# uStatusBoard.net
KiCad netlist of a schematic drawn in EAGLE
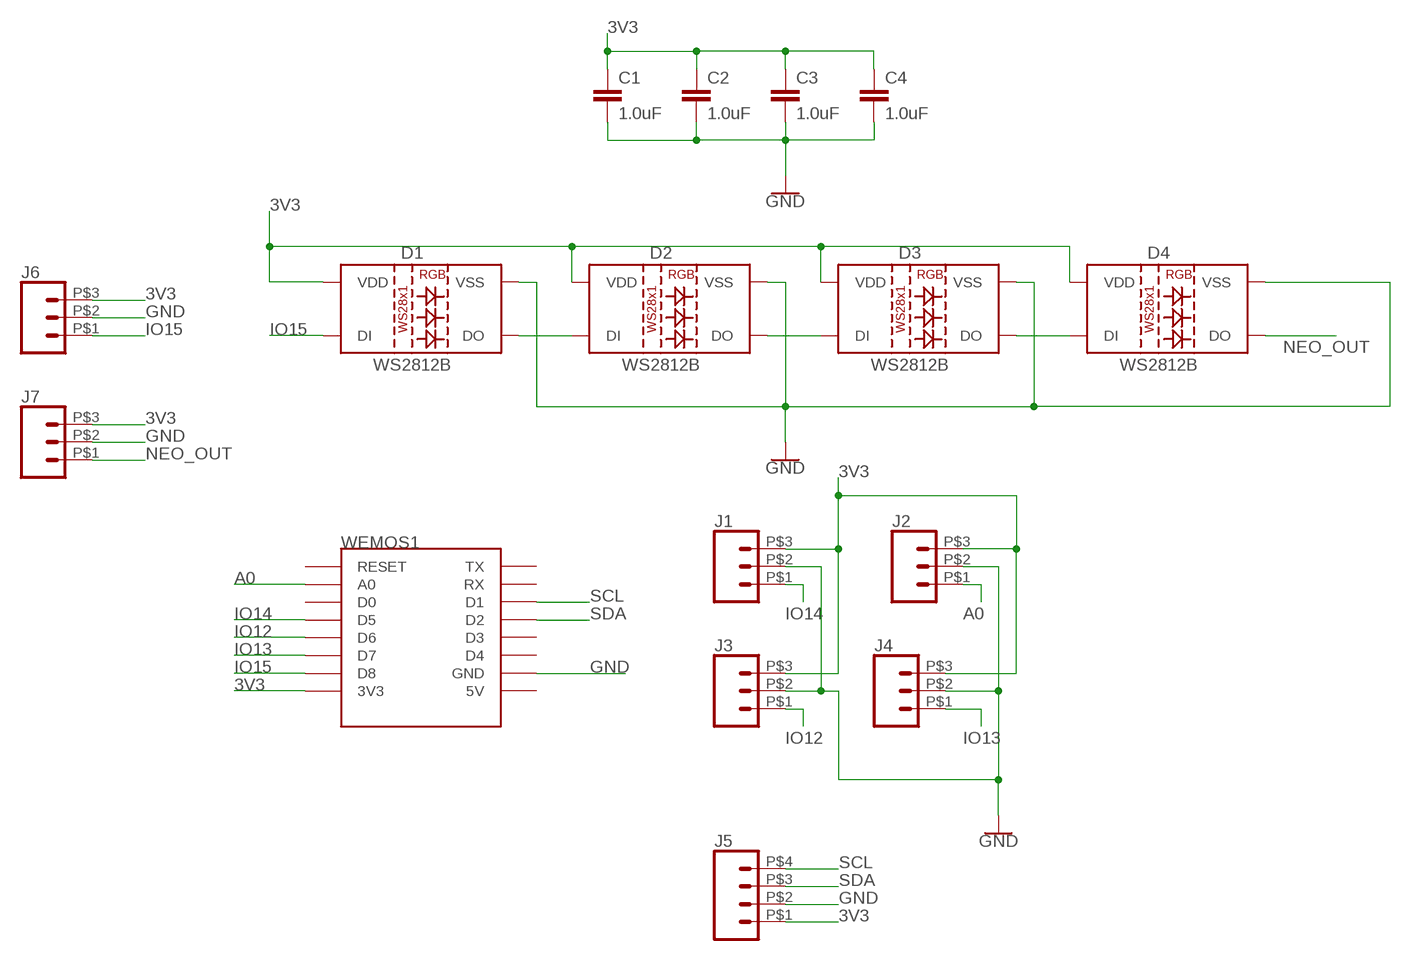
[diagram p0: schematic, sheet 1]

(export (version "E")
  (design (tool "Eeschema 10.0.6"))
  (components
    (comp (ref "C1")
      (value "1.0uF")
      (footprint "eagle-import:0805")
      (libsource (lib "eagle-import") (part "1.0UF-0805-25V-10%"))
    )
    (comp (ref "C2")
      (value "1.0uF")
      (footprint "eagle-import:0805")
      (libsource (lib "eagle-import") (part "1.0UF-0805-25V-10%"))
    )
    (comp (ref "C3")
      (value "1.0uF")
      (footprint "eagle-import:0805")
      (libsource (lib "eagle-import") (part "1.0UF-0805-25V-10%"))
    )
    (comp (ref "C4")
      (value "1.0uF")
      (footprint "eagle-import:0805")
      (libsource (lib "eagle-import") (part "1.0UF-0805-25V-10%"))
    )
    (comp (ref "D1")
      (value "WS2812B")
      (footprint "eagle-import:WS2812B")
      (libsource (lib "eagle-import") (part "WS2812B"))
    )
    (comp (ref "D2")
      (value "WS2812B")
      (footprint "eagle-import:WS2812B")
      (libsource (lib "eagle-import") (part "WS2812B"))
    )
    (comp (ref "D3")
      (value "WS2812B")
      (footprint "eagle-import:WS2812B")
      (libsource (lib "eagle-import") (part "WS2812B"))
    )
    (comp (ref "D4")
      (value "WS2812B")
      (footprint "eagle-import:WS2812B")
      (libsource (lib "eagle-import") (part "WS2812B"))
    )
    (comp (ref "J1")
      (value "CONN_031X03_SMD")
      (footprint "eagle-import:1X03_SMD")
      (libsource (lib "eagle-import") (part "CONN_031X03_SMD"))
    )
    (comp (ref "J2")
      (value "CONN_031X03_SMD")
      (footprint "eagle-import:1X03_SMD")
      (libsource (lib "eagle-import") (part "CONN_031X03_SMD"))
    )
    (comp (ref "J3")
      (value "CONN_031X03_SMD")
      (footprint "eagle-import:1X03_SMD")
      (libsource (lib "eagle-import") (part "CONN_031X03_SMD"))
    )
    (comp (ref "J4")
      (value "CONN_031X03_SMD")
      (footprint "eagle-import:1X03_SMD")
      (libsource (lib "eagle-import") (part "CONN_031X03_SMD"))
    )
    (comp (ref "J5")
      (value "CONN_041X04_SMD")
      (footprint "eagle-import:1X04_SMD")
      (libsource (lib "eagle-import") (part "CONN_041X04_SMD"))
    )
    (comp (ref "J6")
      (value "CONN_031X03_SMD")
      (footprint "eagle-import:1X03_SMD")
      (libsource (lib "eagle-import") (part "CONN_031X03_SMD"))
    )
    (comp (ref "J7")
      (value "CONN_031X03_SMD")
      (footprint "eagle-import:1X03_SMD")
      (libsource (lib "eagle-import") (part "CONN_031X03_SMD"))
    )
    (comp (ref "WEMOS1")
      (value "WEMOS-D1-MINIWEMOS_SMD")
      (footprint "eagle-import:WEMOS-SMD")
      (libsource (lib "eagle-import") (part "WEMOS-D1-MINIWEMOS_SMD"))
    )
  )
  (nets
    (net (code "1") (name "/3V3") (class "Default")
      (node (ref "C1") (pin "1") (pinfunction "1_1") (pintype "passive"))
      (node (ref "C2") (pin "1") (pinfunction "1_1") (pintype "passive"))
      (node (ref "C3") (pin "1") (pinfunction "1_1") (pintype "passive"))
      (node (ref "C4") (pin "1") (pinfunction "1_1") (pintype "passive"))
      (node (ref "D1") (pin "1") (pinfunction "VDD_1") (pintype "bidirectional"))
      (node (ref "D2") (pin "1") (pinfunction "VDD_1") (pintype "bidirectional"))
      (node (ref "D3") (pin "1") (pinfunction "VDD_1") (pintype "bidirectional"))
      (node (ref "D4") (pin "1") (pinfunction "VDD_1") (pintype "bidirectional"))
      (node (ref "J1") (pin "P$3") (pinfunction "3_P$3") (pintype "passive"))
      (node (ref "J2") (pin "P$3") (pinfunction "3_P$3") (pintype "passive"))
      (node (ref "J3") (pin "P$3") (pinfunction "3_P$3") (pintype "passive"))
      (node (ref "J4") (pin "P$3") (pinfunction "3_P$3") (pintype "passive"))
      (node (ref "J5") (pin "P$1") (pinfunction "1_P$1") (pintype "passive"))
      (node (ref "J6") (pin "P$3") (pinfunction "3_P$3") (pintype "passive"))
      (node (ref "J7") (pin "P$3") (pinfunction "3_P$3") (pintype "passive"))
      (node (ref "WEMOS1") (pin "3V3") (pinfunction "3V3_3V3") (pintype "bidirectional"))
    )
    (net (code "2") (name "/A0") (class "Default")
      (node (ref "J2") (pin "P$1") (pinfunction "1_P$1") (pintype "passive"))
      (node (ref "WEMOS1") (pin "A0") (pinfunction "A0_A0") (pintype "bidirectional"))
    )
    (net (code "3") (name "/IO12") (class "Default")
      (node (ref "J3") (pin "P$1") (pinfunction "1_P$1") (pintype "passive"))
      (node (ref "WEMOS1") (pin "D6") (pinfunction "D6_D6") (pintype "bidirectional"))
    )
    (net (code "4") (name "/IO13") (class "Default")
      (node (ref "J4") (pin "P$1") (pinfunction "1_P$1") (pintype "passive"))
      (node (ref "WEMOS1") (pin "D7") (pinfunction "D7_D7") (pintype "bidirectional"))
    )
    (net (code "5") (name "/IO14") (class "Default")
      (node (ref "J1") (pin "P$1") (pinfunction "1_P$1") (pintype "passive"))
      (node (ref "WEMOS1") (pin "D5") (pinfunction "D5_D5") (pintype "bidirectional"))
    )
    (net (code "6") (name "/IO15") (class "Default")
      (node (ref "D1") (pin "4") (pinfunction "DI_4") (pintype "bidirectional"))
      (node (ref "J6") (pin "P$1") (pinfunction "1_P$1") (pintype "passive"))
      (node (ref "WEMOS1") (pin "D8") (pinfunction "D8_D8") (pintype "bidirectional"))
    )
    (net (code "7") (name "/NEO_OUT") (class "Default")
      (node (ref "D4") (pin "2") (pinfunction "DO_2") (pintype "bidirectional"))
      (node (ref "J7") (pin "P$1") (pinfunction "1_P$1") (pintype "passive"))
    )
    (net (code "8") (name "/SCL") (class "Default")
      (node (ref "J5") (pin "P$4") (pinfunction "4_P$4") (pintype "passive"))
      (node (ref "WEMOS1") (pin "D1") (pinfunction "D1_D1") (pintype "bidirectional"))
    )
    (net (code "9") (name "/SDA") (class "Default")
      (node (ref "J5") (pin "P$3") (pinfunction "3_P$3") (pintype "passive"))
      (node (ref "WEMOS1") (pin "D2") (pinfunction "D2_D2") (pintype "bidirectional"))
    )
    (net (code "10") (name "GND") (class "Default")
      (node (ref "C1") (pin "2") (pinfunction "2_2") (pintype "passive"))
      (node (ref "C2") (pin "2") (pinfunction "2_2") (pintype "passive"))
      (node (ref "C3") (pin "2") (pinfunction "2_2") (pintype "passive"))
      (node (ref "C4") (pin "2") (pinfunction "2_2") (pintype "passive"))
      (node (ref "D1") (pin "3") (pinfunction "VSS_3") (pintype "bidirectional"))
      (node (ref "D2") (pin "3") (pinfunction "VSS_3") (pintype "bidirectional"))
      (node (ref "D3") (pin "3") (pinfunction "VSS_3") (pintype "bidirectional"))
      (node (ref "D4") (pin "3") (pinfunction "VSS_3") (pintype "bidirectional"))
      (node (ref "J1") (pin "P$2") (pinfunction "2_P$2") (pintype "passive"))
      (node (ref "J2") (pin "P$2") (pinfunction "2_P$2") (pintype "passive"))
      (node (ref "J3") (pin "P$2") (pinfunction "2_P$2") (pintype "passive"))
      (node (ref "J4") (pin "P$2") (pinfunction "2_P$2") (pintype "passive"))
      (node (ref "J5") (pin "P$2") (pinfunction "2_P$2") (pintype "passive"))
      (node (ref "J6") (pin "P$2") (pinfunction "2_P$2") (pintype "passive"))
      (node (ref "J7") (pin "P$2") (pinfunction "2_P$2") (pintype "passive"))
      (node (ref "WEMOS1") (pin "GND") (pinfunction "GND_GND") (pintype "bidirectional"))
    )
    (net (code "11") (name "Net-(D1-DO)") (class "Default")
      (node (ref "D1") (pin "2") (pinfunction "DO_2") (pintype "bidirectional"))
      (node (ref "D2") (pin "4") (pinfunction "DI_4") (pintype "bidirectional"))
    )
    (net (code "12") (name "Net-(D2-DO)") (class "Default")
      (node (ref "D2") (pin "2") (pinfunction "DO_2") (pintype "bidirectional"))
      (node (ref "D3") (pin "4") (pinfunction "DI_4") (pintype "bidirectional"))
    )
    (net (code "13") (name "Net-(D3-DO)") (class "Default")
      (node (ref "D3") (pin "2") (pinfunction "DO_2") (pintype "bidirectional"))
      (node (ref "D4") (pin "4") (pinfunction "DI_4") (pintype "bidirectional"))
    )
    (net (code "14") (name "unconnected-(WEMOS1-Pad5V)") (class "Default")
      (node (ref "WEMOS1") (pin "5V") (pinfunction "5V_5V") (pintype "bidirectional"))
    )
    (net (code "15") (name "unconnected-(WEMOS1-PadD0)") (class "Default")
      (node (ref "WEMOS1") (pin "D0") (pinfunction "D0_D0") (pintype "bidirectional"))
    )
    (net (code "16") (name "unconnected-(WEMOS1-PadD3)") (class "Default")
      (node (ref "WEMOS1") (pin "D3") (pinfunction "D3_D3") (pintype "bidirectional"))
    )
    (net (code "17") (name "unconnected-(WEMOS1-PadD4)") (class "Default")
      (node (ref "WEMOS1") (pin "D4") (pinfunction "D4_D4") (pintype "bidirectional"))
    )
    (net (code "18") (name "unconnected-(WEMOS1-PadRESET)") (class "Default")
      (node (ref "WEMOS1") (pin "RESET") (pinfunction "RESET_RESET") (pintype "bidirectional"))
    )
    (net (code "19") (name "unconnected-(WEMOS1-PadRX)") (class "Default")
      (node (ref "WEMOS1") (pin "RX") (pinfunction "RX_RX") (pintype "bidirectional"))
    )
    (net (code "20") (name "unconnected-(WEMOS1-PadTX)") (class "Default")
      (node (ref "WEMOS1") (pin "TX") (pinfunction "TX_TX") (pintype "bidirectional"))
    )
  )
)
